# YW_001.net
KiCad netlist of a schematic drawn in Altium Designer
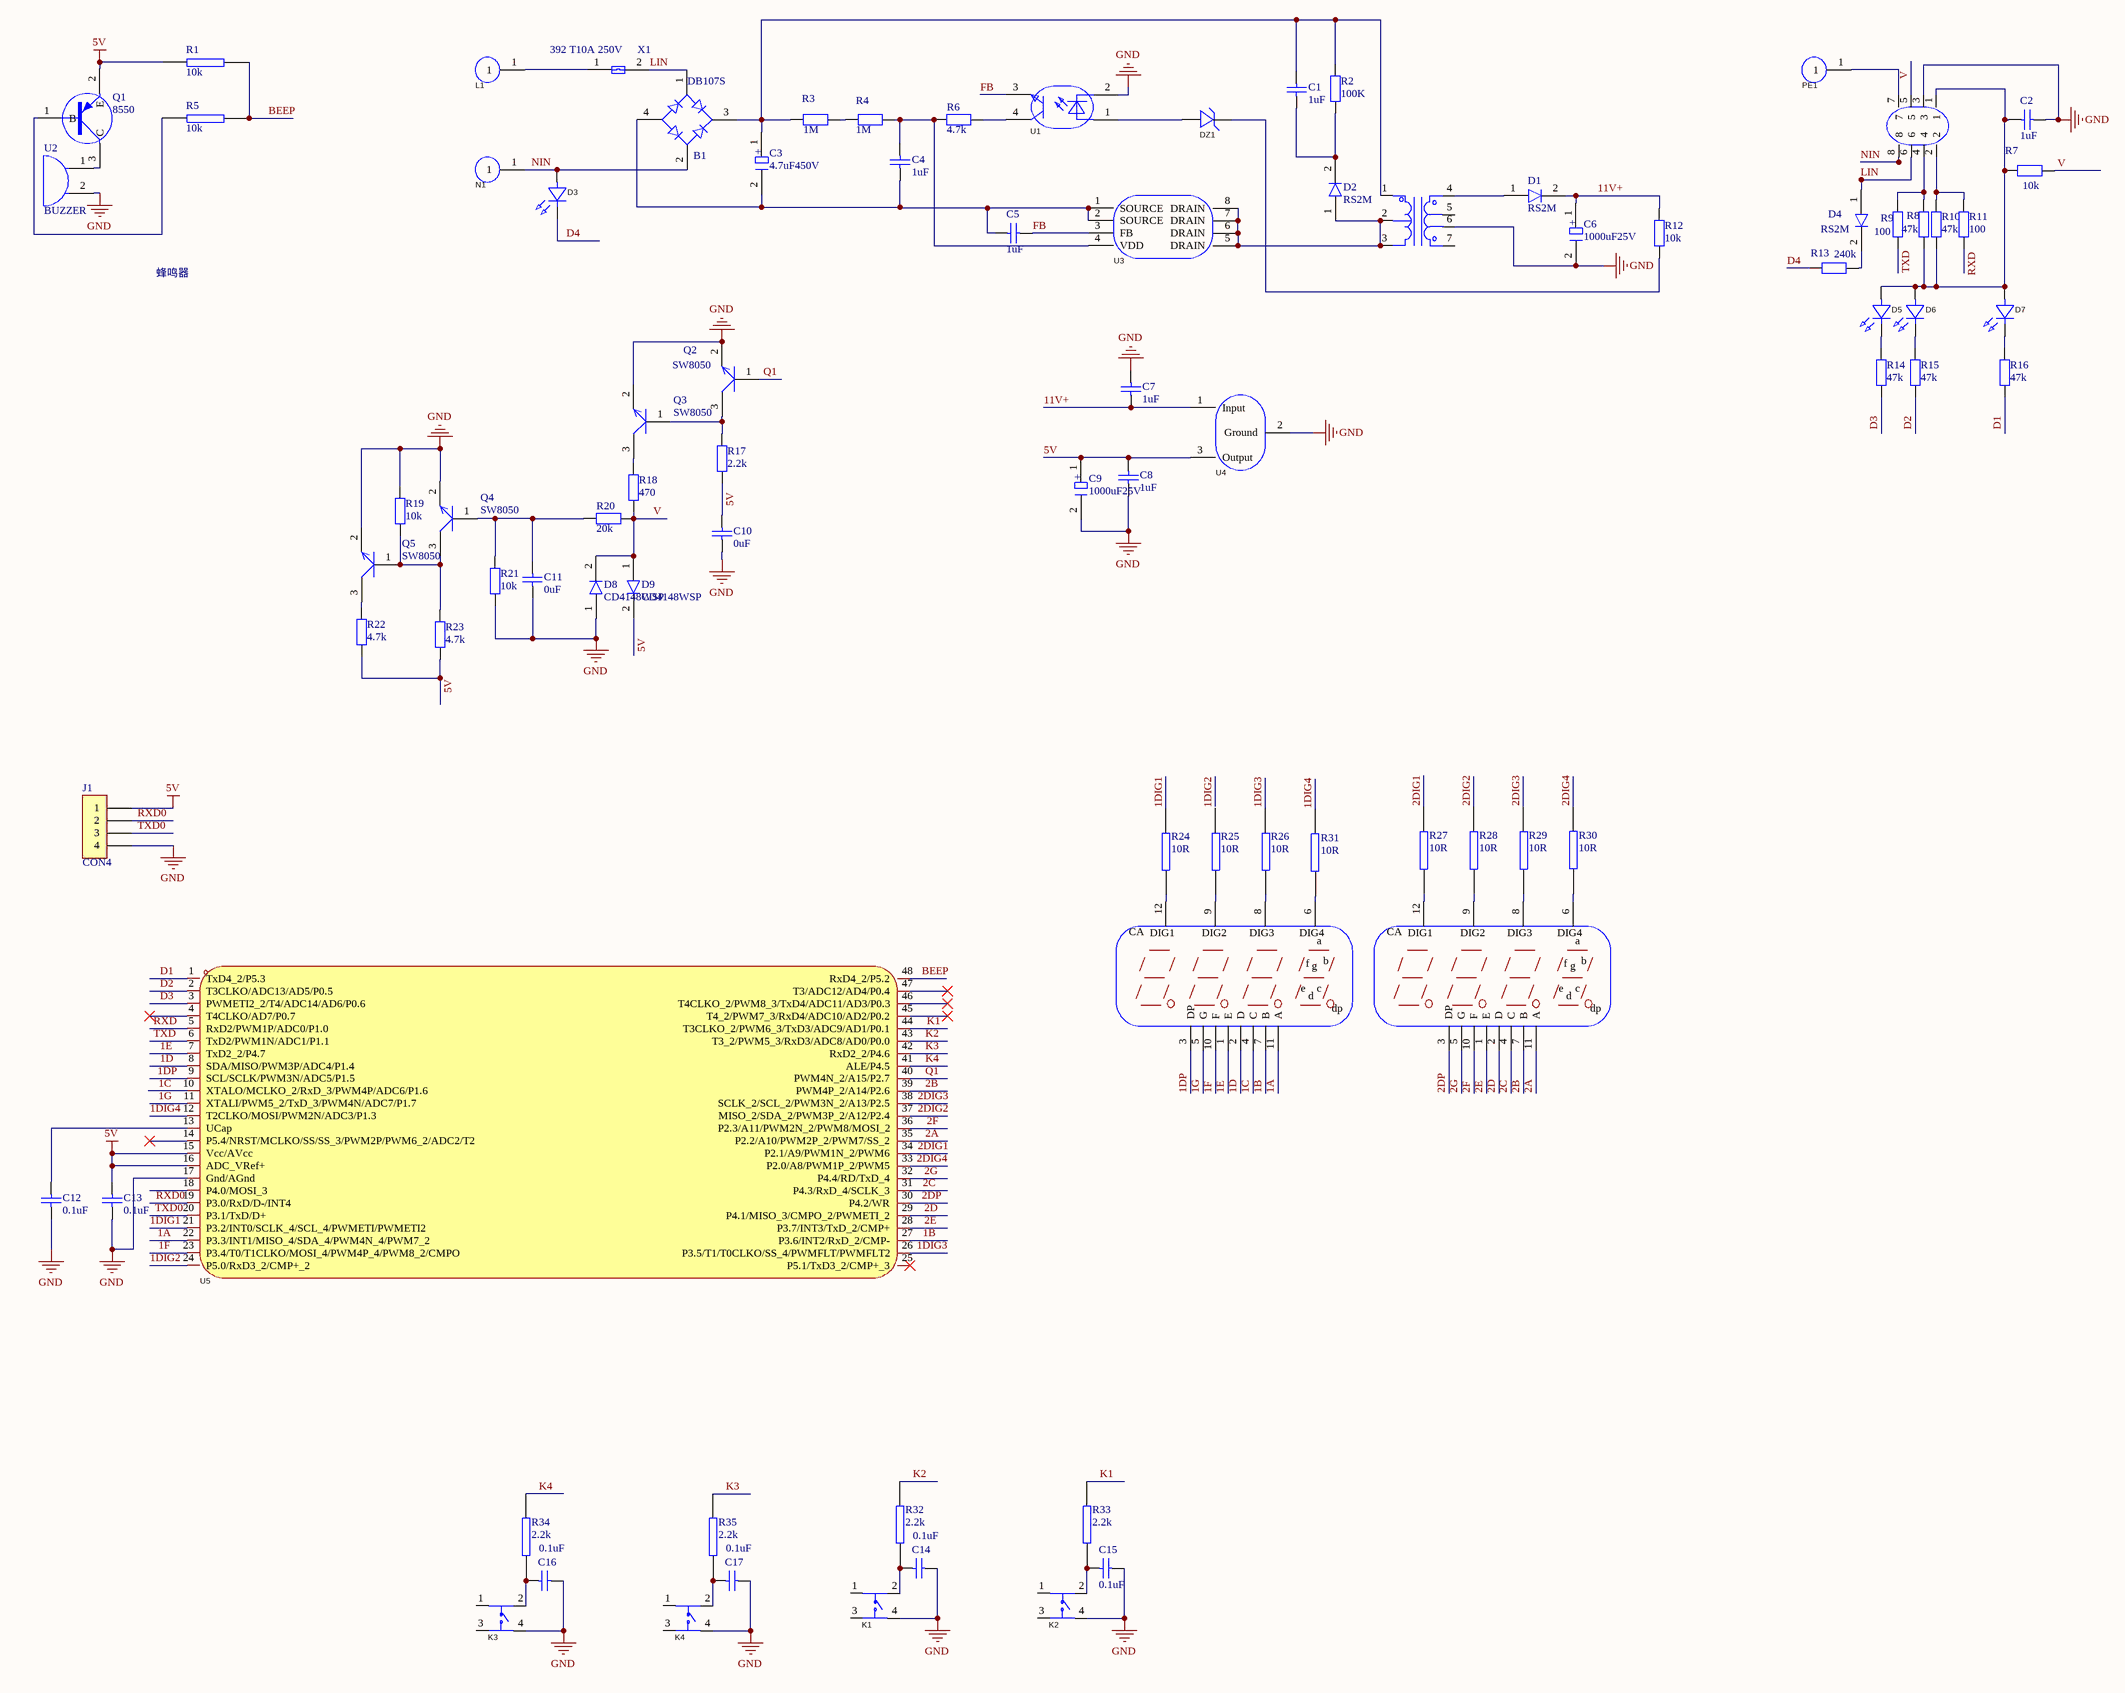
[diagram p0: YW_001.SchDoc]

(export (version "E")
  (design (tool "Eeschema 10.0.6"))
  (components
    (comp (ref "B1") (value "DB107S") (footprint "DB107S") (libsource (lib "*") (part "整流桥堆")))
    (comp (ref "C1")
      (value "1uF")
      (footprint "CAP-TH_L5.5-W4.0-P5.00-D0.5")
      (description "Capacitor")
      (fields (field (name "Comment") "102") (field (name "PUBLISHER") "Altium Limited"))
      (libsource (lib "*") (part "Cap"))
    )
    (comp (ref "C2")
      (value "1uF")
      (footprint "0805C")
      (description "Capacitor")
      (fields (field (name "Comment") "104P") (field (name "PUBLISHER") "Altium Limited"))
      (libsource (lib "*") (part "Cap"))
    )
    (comp (ref "C3")
      (value "4.7uF450V")
      (footprint "CAP-TH_BD6.3-P2.50-D1.0-FD")
      (libsource (lib "*") (part "电解电容"))
    )
    (comp (ref "C4")
      (value "1uF")
      (footprint "0805C")
      (description "Capacitor")
      (fields (field (name "PUBLISHER") "Altium Limited"))
      (libsource (lib "*") (part "Cap"))
    )
    (comp (ref "C5")
      (value "1uF")
      (footprint "0805C")
      (description "Capacitor")
      (fields (field (name "Comment") "104P") (field (name "PUBLISHER") "Altium Limited"))
      (libsource (lib "*") (part "Cap"))
    )
    (comp (ref "C6")
      (value "1000uF25V")
      (footprint "CAP-TH_BD10.0-P5.00-D1.0-FD")
      (description "CD2881081EM1017VFL")
      (libsource (lib "*") (part "电解电容"))
    )
    (comp (ref "C7")
      (value "1uF")
      (footprint "0805C")
      (description "Capacitor")
      (fields (field (name "Comment") "102") (field (name "PUBLISHER") "Altium Limited"))
      (libsource (lib "*") (part "Cap"))
    )
    (comp (ref "C8")
      (value "1uF")
      (footprint "0805C")
      (description "Capacitor")
      (fields (field (name "PUBLISHER") "Altium Limited"))
      (libsource (lib "*") (part "Cap"))
    )
    (comp (ref "C9")
      (value "1000uF25V")
      (footprint "CAP-TH_BD10.0-P5.00-D1.0-FD")
      (description "CD2881081EM1017VFL")
      (libsource (lib "*") (part "电解电容"))
    )
    (comp (ref "C10")
      (value "0uF")
      (footprint "0805C")
      (description "Capacitor")
      (fields (field (name "Comment") "102") (field (name "PUBLISHER") "Altium Limited"))
      (libsource (lib "*") (part "Cap"))
    )
    (comp (ref "C11")
      (value "0uF")
      (footprint "0805C")
      (description "Capacitor")
      (fields (field (name "Comment") "102") (field (name "PUBLISHER") "Altium Limited"))
      (libsource (lib "*") (part "Cap"))
    )
    (comp (ref "C12")
      (value "0.1uF")
      (footprint "C0603")
      (description "Capacitor")
      (fields (field (name "Comment") "104P") (field (name "PUBLISHER") "Altium Limited"))
      (libsource (lib "*") (part "Cap"))
    )
    (comp (ref "C13")
      (value "0.1uF")
      (footprint "C0603")
      (description "Capacitor")
      (fields (field (name "Comment") "104P") (field (name "PUBLISHER") "Altium Limited"))
      (libsource (lib "*") (part "Cap"))
    )
    (comp (ref "C14")
      (value "0.1uF")
      (footprint "0805C")
      (description "Capacitor")
      (fields (field (name "Comment") "104P") (field (name "PUBLISHER") "Altium Limited"))
      (libsource (lib "*") (part "Cap"))
    )
    (comp (ref "C15")
      (value "0.1uF")
      (footprint "0805C")
      (description "Capacitor")
      (fields (field (name "Comment") "104P") (field (name "PUBLISHER") "Altium Limited"))
      (libsource (lib "*") (part "Cap"))
    )
    (comp (ref "C16")
      (value "0.1uF")
      (footprint "0805C")
      (description "Capacitor")
      (fields (field (name "Comment") "104P") (field (name "PUBLISHER") "Altium Limited"))
      (libsource (lib "*") (part "Cap"))
    )
    (comp (ref "C17")
      (value "0.1uF")
      (footprint "0805C")
      (description "Capacitor")
      (fields (field (name "Comment") "104P") (field (name "PUBLISHER") "Altium Limited"))
      (libsource (lib "*") (part "Cap"))
    )
    (comp (ref "D1")
      (value "RS2M")
      (footprint "SMA-SMD_L4.4-W2.7-LS5.4-RD")
      (libsource (lib "CAMERON") (part "二极管"))
    )
    (comp (ref "D2")
      (value "RS2M")
      (footprint "SMA-SMD_L4.4-W2.7-LS5.4-RD")
      (libsource (lib "CAMERON") (part "二极管"))
    )
    (comp (ref "D3")
      (value "HLMP-1503-D0000")
      (footprint "LED-TH_BD3.0-P2.54-RD")
      (fields (field (name "MANUFACTURER") "Broadcom/AVAGO(安华高)"))
      (libsource (lib "CAMERON") (part "HLMP-1503-D0000"))
    )
    (comp (ref "D4")
      (value "RS2M")
      (footprint "SMA-SMD_L4.4-W2.7-LS5.4-RD")
      (libsource (lib "CAMERON") (part "二极管"))
    )
    (comp (ref "D5")
      (value "HLMP-1503-D0000")
      (footprint "LED-TH_BD3.0-P2.54-RD")
      (fields (field (name "MANUFACTURER") "Broadcom/AVAGO(安华高)"))
      (libsource (lib "CAMERON") (part "HLMP-1503-D0000"))
    )
    (comp (ref "D6")
      (value "HLMP-1503-D0000")
      (footprint "LED-TH_BD3.0-P2.54-RD")
      (fields (field (name "MANUFACTURER") "Broadcom/AVAGO(安华高)"))
      (libsource (lib "CAMERON") (part "HLMP-1503-D0000"))
    )
    (comp (ref "D7")
      (value "HLMP-1503-D0000")
      (footprint "LED-TH_BD3.0-P2.54-RD")
      (fields (field (name "MANUFACTURER") "Broadcom/AVAGO(安华高)"))
      (libsource (lib "CAMERON") (part "HLMP-1503-D0000"))
    )
    (comp (ref "D8") (value "CD4148WSP") (footprint "D0805-RD") (libsource (lib "CAMERON") (part "二极管")))
    (comp (ref "D9") (value "CD4148WSP") (footprint "D0805-RD") (libsource (lib "CAMERON") (part "二极管")))
    (comp (ref "DZ1")
      (value "ZMM24")
      (footprint "LL-34_L3.5-W1.5-RD")
      (fields (field (name "MANUFACTURER") "HXY MOSFET(华轩阳电子)"))
      (libsource (lib "CAMERON") (part "ZMM24_C7470923"))
    )
    (comp (ref "H1")
      (value "HC-5557-2*4AW")
      (footprint "CONN-TH_8P-P4.20_5557-2X4AW")
      (fields (field (name "MANUFACTURER") "HCTL(华灿天禄)"))
      (libsource (lib "CAMERON") (part "HC-5557-2*4AW"))
    )
    (comp (ref "J1")
      (value "CON4")
      (footprint "HDR1X4")
      (description "Connector")
      (libsource (lib "*") (part "CON4"))
    )
    (comp (ref "K1")
      (value "TS1212TPFS 250gf 072")
      (footprint "KEY-SMD_4P-L12.0-W12.0-P5.00-LS15.0")
      (fields (field (name "MANUFACTURER") "SHOU HAN(首韩)"))
      (libsource (lib "CAMERON") (part "TS1212TPFS 250gf 072"))
    )
    (comp (ref "K2")
      (value "TS1212TPFS 250gf 072")
      (footprint "KEY-SMD_4P-L12.0-W12.0-P5.00-LS15.0")
      (fields (field (name "MANUFACTURER") "SHOU HAN(首韩)"))
      (libsource (lib "CAMERON") (part "TS1212TPFS 250gf 072"))
    )
    (comp (ref "K3")
      (value "TS1212TPFS 250gf 072")
      (footprint "KEY-SMD_4P-L12.0-W12.0-P5.00-LS15.0")
      (fields (field (name "MANUFACTURER") "SHOU HAN(首韩)"))
      (libsource (lib "CAMERON") (part "TS1212TPFS 250gf 072"))
    )
    (comp (ref "K4")
      (value "TS1212TPFS 250gf 072")
      (footprint "KEY-SMD_4P-L12.0-W12.0-P5.00-LS15.0")
      (fields (field (name "MANUFACTURER") "SHOU HAN(首韩)"))
      (libsource (lib "CAMERON") (part "TS1212TPFS 250gf 072"))
    )
    (comp (ref "L1")
      (value "PZ254V-11-01P")
      (footprint "HDR-TH_1P-P2.54-V-M")
      (fields (field (name "MANUFACTURER") "XFCN(兴飞)"))
      (libsource (lib "CAMERON") (part "PZ254V-11-01P"))
    )
    (comp (ref "LED1")
      (value "FJ5461BH 橙红")
      (footprint "LED-SEG-TH_FJ5461AH")
      (fields (field (name "MANUFACTURER") "志浩"))
      (libsource (lib "CAMERON") (part "FJ5461BH 橙红"))
    )
    (comp (ref "LED2")
      (value "FJ5461BH 橙红")
      (footprint "LED-SEG-TH_FJ5461AH")
      (fields (field (name "MANUFACTURER") "志浩"))
      (libsource (lib "CAMERON") (part "FJ5461BH 橙红"))
    )
    (comp (ref "N1")
      (value "PZ254V-11-01P")
      (footprint "HDR-TH_1P-P2.54-V-M")
      (fields (field (name "MANUFACTURER") "XFCN(兴飞)"))
      (libsource (lib "altium-import") (part "root_2_PZ254V-11-01P_"))
    )
    (comp (ref "PE1")
      (value "PZ254V-11-01P")
      (footprint "HDR-TH_1P-P2.54-V-M")
      (fields (field (name "MANUFACTURER") "XFCN(兴飞)"))
      (libsource (lib "CAMERON") (part "PZ254V-11-01P"))
    )
    (comp (ref "Q1") (value "8550") (footprint "SOT-23") (libsource (lib "*") (part "PNP")))
    (comp (ref "Q2")
      (value "SW8050")
      (footprint "SOT-23 - S8550")
      (libsource (lib "CAMERON") (part "普通三级管（NPN）"))
    )
    (comp (ref "Q3")
      (value "SW8050")
      (footprint "SOT-23 - S8550")
      (libsource (lib "CAMERON") (part "普通三级管（NPN）"))
    )
    (comp (ref "Q4")
      (value "SW8050")
      (footprint "SOT-23 - S8550")
      (libsource (lib "CAMERON") (part "普通三级管（NPN）"))
    )
    (comp (ref "Q5")
      (value "SW8050")
      (footprint "SOT-23 - S8550")
      (libsource (lib "CAMERON") (part "普通三级管（NPN）"))
    )
    (comp (ref "R1") (value "10k") (footprint "0805") (libsource (lib "*") (part "RES2")))
    (comp (ref "R2")
      (value "100K")
      (footprint "0805")
      (description "Resistor")
      (fields (field (name "Comment") "Res2") (field (name "PUBLISHER") "Altium Limited"))
      (libsource (lib "") (part "Res2_1"))
    )
    (comp (ref "R3")
      (value "1M")
      (footprint "0805")
      (description "Resistor")
      (fields (field (name "Comment") "Res2") (field (name "PUBLISHER") "Altium Limited"))
      (libsource (lib "*") (part "Res2"))
    )
    (comp (ref "R4")
      (value "1M")
      (footprint "0805")
      (description "Resistor")
      (fields (field (name "Comment") "Res2") (field (name "PUBLISHER") "Altium Limited"))
      (libsource (lib "*") (part "Res2"))
    )
    (comp (ref "R5") (value "10k") (footprint "0805") (libsource (lib "*") (part "RES2")))
    (comp (ref "R6")
      (value "4.7k")
      (footprint "0805")
      (description "Resistor")
      (fields (field (name "Comment") "Res2") (field (name "PUBLISHER") "Altium Limited"))
      (libsource (lib "*") (part "Res2"))
    )
    (comp (ref "R7")
      (value "10k")
      (footprint "0805")
      (description "Resistor")
      (fields (field (name "Comment") "Res2") (field (name "PUBLISHER") "Altium Limited"))
      (libsource (lib "*") (part "Res2"))
    )
    (comp (ref "R8")
      (value "47k")
      (footprint "0805")
      (description "Resistor")
      (fields (field (name "Comment") "Res2") (field (name "PUBLISHER") "Altium Limited"))
      (libsource (lib "") (part "Res2_1"))
    )
    (comp (ref "R9")
      (value "100")
      (footprint "0805")
      (description "Resistor")
      (fields (field (name "Comment") "Res2") (field (name "PUBLISHER") "Altium Limited"))
      (libsource (lib "") (part "Res2_2"))
    )
    (comp (ref "R10")
      (value "47k")
      (footprint "0805")
      (description "Resistor")
      (fields (field (name "Comment") "Res2") (field (name "PUBLISHER") "Altium Limited"))
      (libsource (lib "") (part "Res2_1"))
    )
    (comp (ref "R11")
      (value "100")
      (footprint "0805")
      (description "Resistor")
      (fields (field (name "Comment") "Res2") (field (name "PUBLISHER") "Altium Limited"))
      (libsource (lib "") (part "Res2_2"))
    )
    (comp (ref "R12")
      (value "10k")
      (footprint "0805")
      (description "Resistor")
      (fields (field (name "Comment") "Res2") (field (name "PUBLISHER") "Altium Limited"))
      (libsource (lib "") (part "Res2_1"))
    )
    (comp (ref "R13")
      (value "240k")
      (footprint "0805")
      (description "Resistor")
      (fields (field (name "Comment") "Res2") (field (name "PUBLISHER") "Altium Limited"))
      (libsource (lib "*") (part "Res2"))
    )
    (comp (ref "R14")
      (value "47k")
      (footprint "0805")
      (description "Resistor")
      (fields (field (name "Comment") "Res2") (field (name "PUBLISHER") "Altium Limited"))
      (libsource (lib "") (part "Res2_1"))
    )
    (comp (ref "R15")
      (value "47k")
      (footprint "0805")
      (description "Resistor")
      (fields (field (name "Comment") "Res2") (field (name "PUBLISHER") "Altium Limited"))
      (libsource (lib "") (part "Res2_1"))
    )
    (comp (ref "R16")
      (value "47k")
      (footprint "0805")
      (description "Resistor")
      (fields (field (name "Comment") "Res2") (field (name "PUBLISHER") "Altium Limited"))
      (libsource (lib "") (part "Res2_1"))
    )
    (comp (ref "R17")
      (value "2.2k")
      (footprint "0805")
      (description "Resistor")
      (fields (field (name "Comment") "Res2") (field (name "PUBLISHER") "Altium Limited"))
      (libsource (lib "") (part "Res2_1"))
    )
    (comp (ref "R18")
      (value "470")
      (footprint "0805")
      (description "Resistor")
      (fields (field (name "Comment") "Res2") (field (name "PUBLISHER") "Altium Limited"))
      (libsource (lib "") (part "Res2_1"))
    )
    (comp (ref "R19")
      (value "10k")
      (footprint "0805")
      (description "Resistor")
      (fields (field (name "Comment") "Res2") (field (name "PUBLISHER") "Altium Limited"))
      (libsource (lib "") (part "Res2_1"))
    )
    (comp (ref "R20")
      (value "20k")
      (footprint "0805")
      (description "Resistor")
      (fields (field (name "Comment") "Res2") (field (name "PUBLISHER") "Altium Limited"))
      (libsource (lib "") (part "Res2_3"))
    )
    (comp (ref "R21")
      (value "10k")
      (footprint "0805")
      (description "Resistor")
      (fields (field (name "Comment") "Res2") (field (name "PUBLISHER") "Altium Limited"))
      (libsource (lib "") (part "Res2_2"))
    )
    (comp (ref "R22")
      (value "4.7k")
      (footprint "0805")
      (description "Resistor")
      (fields (field (name "Comment") "Res2") (field (name "PUBLISHER") "Altium Limited"))
      (libsource (lib "") (part "Res2_1"))
    )
    (comp (ref "R23")
      (value "4.7k")
      (footprint "0805")
      (description "Resistor")
      (fields (field (name "Comment") "Res2") (field (name "PUBLISHER") "Altium Limited"))
      (libsource (lib "") (part "Res2_1"))
    )
    (comp (ref "R24") (value "10R") (footprint "R0603") (libsource (lib "*") (part "RES2")))
    (comp (ref "R25") (value "10R") (footprint "R0603") (libsource (lib "*") (part "RES2")))
    (comp (ref "R26") (value "10R") (footprint "R0603") (libsource (lib "*") (part "RES2")))
    (comp (ref "R27") (value "10R") (footprint "R0603") (libsource (lib "*") (part "RES2")))
    (comp (ref "R28") (value "10R") (footprint "R0603") (libsource (lib "*") (part "RES2")))
    (comp (ref "R29") (value "10R") (footprint "R0603") (libsource (lib "*") (part "RES2")))
    (comp (ref "R30") (value "10R") (footprint "R0603") (libsource (lib "*") (part "RES2")))
    (comp (ref "R31") (value "10R") (footprint "R0603") (libsource (lib "*") (part "RES2")))
    (comp (ref "R32") (value "2.2k") (footprint "0805") (libsource (lib "*") (part "RES2")))
    (comp (ref "R33") (value "2.2k") (footprint "0805") (libsource (lib "*") (part "RES2")))
    (comp (ref "R34") (value "2.2k") (footprint "0805") (libsource (lib "*") (part "RES2")))
    (comp (ref "R35") (value "2.2k") (footprint "0805") (libsource (lib "*") (part "RES2")))
    (comp (ref "U1")
      (value "EL817S1(C)(TU)-F")
      (footprint "OPTO-SMD-4_L4.6-W6.5-P2.54-LS10.3-TL")
      (fields (field (name "MANUFACTURER") "EVERLIGHT(亿光)"))
      (libsource (lib "CAMERON") (part "EL817S1(C)(TU)-F"))
    )
    (comp (ref "U2")
      (value "BUZZER")
      (footprint "BUZZ-7.6/12")
      (description "Buzzer")
      (libsource (lib "*") (part "BUZZER"))
    )
    (comp (ref "U3")
      (value "VIPER12ASTR-E")
      (footprint "SOIC-8_L5.0-W4.0-P1.27-LS6.0-BL")
      (fields (field (name "MANUFACTURER") "ST(意法半导体)"))
      (libsource (lib "CAMERON") (part "VIPER12ASTR-E"))
    )
    (comp (ref "U4")
      (value "MC7805CDTRKG")
      (footprint "TO-252-2_L6.6-W6.1-P4.58-LS9.9-TL")
      (fields (field (name "MANUFACTURER") "onsemi(安森美)"))
      (libsource (lib "CAMERON") (part "MC7805CDTRKG"))
    )
    (comp (ref "U5")
      (value "STC8H8K64U-45I-LQFP48")
      (footprint "LQFP-48_L7.0-W7.0-P0.50-LS9.0-BL")
      (fields (field (name "MANUFACTURER") "STC(宏晶)"))
      (libsource (lib "CAMERON") (part "STC8H8K64U-45I-LQFP48"))
    )
    (comp (ref "USB1")
      (value "ECO2017SEO-X16V015")
      (footprint "XFMR-TH_ECO2017SEO-X16V015")
      (fields (field (name "MANUFACTURER") "TDK"))
      (libsource (lib "CAMERON") (part "ECO2017SEO-X16V015"))
    )
    (comp (ref "X1") (value "392 T10A 250V") (footprint "FUSE") (libsource (lib "*") (part "保险丝")))
  )
  (nets
    (net (code "1") (name "/1A") (class "Default")
      (node (ref "LED1") (pin "11") (pinfunction "A_11") (pintype "passive"))
      (node (ref "U5") (pin "22") (pinfunction "P3.3/INT1/MISO_4/SDA_4/PWM4N_4/PWM7_2_22") (pintype "passive"))
    )
    (net (code "2") (name "/1B") (class "Default")
      (node (ref "LED1") (pin "7") (pinfunction "B_7") (pintype "passive"))
      (node (ref "U5") (pin "27") (pinfunction "P3.6/INT2/RxD_2/CMP-_27") (pintype "passive"))
    )
    (net (code "3") (name "/1C") (class "Default")
      (node (ref "LED1") (pin "4") (pinfunction "C_4") (pintype "passive"))
      (node (ref "U5") (pin "10") (pinfunction "XTALO/MCLKO_2/RxD_3/PWM4P/ADC6/P1.6_10") (pintype "passive"))
    )
    (net (code "4") (name "/1D") (class "Default")
      (node (ref "LED1") (pin "2") (pinfunction "D_2") (pintype "passive"))
      (node (ref "U5") (pin "8") (pinfunction "SDA/MISO/PWM3P/ADC4/P1.4_8") (pintype "passive"))
    )
    (net (code "5") (name "/1DIG1") (class "Default")
      (node (ref "R24") (pin "1") (pinfunction "1_1") (pintype "passive"))
      (node (ref "U5") (pin "21") (pinfunction "P3.2/INT0/SCLK_4/SCL_4/PWMETI/PWMETI2_21") (pintype "passive"))
    )
    (net (code "6") (name "/1DIG2") (class "Default")
      (node (ref "R25") (pin "1") (pinfunction "1_1") (pintype "passive"))
      (node (ref "U5") (pin "24") (pinfunction "P5.0/RxD3_2/CMP+_2_24") (pintype "passive"))
    )
    (net (code "7") (name "/1DIG3") (class "Default")
      (node (ref "R26") (pin "1") (pinfunction "1_1") (pintype "passive"))
      (node (ref "U5") (pin "26") (pinfunction "P3.5/T1/T0CLKO/SS_4/PWMFLT/PWMFLT2_26") (pintype "passive"))
    )
    (net (code "8") (name "/1DIG4") (class "Default")
      (node (ref "R31") (pin "2") (pinfunction "2_2") (pintype "passive"))
      (node (ref "U5") (pin "12") (pinfunction "T2CLKO/MOSI/PWM2N/ADC3/P1.3_12") (pintype "passive"))
    )
    (net (code "9") (name "/1DP") (class "Default")
      (node (ref "LED1") (pin "3") (pinfunction "DP_3") (pintype "passive"))
      (node (ref "U5") (pin "9") (pinfunction "SCL/SCLK/PWM3N/ADC5/P1.5_9") (pintype "passive"))
    )
    (net (code "10") (name "/1E") (class "Default")
      (node (ref "LED1") (pin "1") (pinfunction "E_1") (pintype "passive"))
      (node (ref "U5") (pin "7") (pinfunction "TxD2_2/P4.7_7") (pintype "passive"))
    )
    (net (code "11") (name "/1F") (class "Default")
      (node (ref "LED1") (pin "10") (pinfunction "F_10") (pintype "passive"))
      (node (ref "U5") (pin "23") (pinfunction "P3.4/T0/T1CLKO/MOSI_4/PWM4P_4/PWM8_2/CMPO_23") (pintype "passive"))
    )
    (net (code "12") (name "/1G") (class "Default")
      (node (ref "LED1") (pin "5") (pinfunction "G_5") (pintype "passive"))
      (node (ref "U5") (pin "11") (pinfunction "XTALI/PWM5_2/TxD_3/PWM4N/ADC7/P1.7_11") (pintype "passive"))
    )
    (net (code "13") (name "/2A") (class "Default")
      (node (ref "LED2") (pin "11") (pinfunction "A_11") (pintype "passive"))
      (node (ref "U5") (pin "35") (pinfunction "P2.2/A10/PWM2P_2/PWM7/SS_2_35") (pintype "passive"))
    )
    (net (code "14") (name "/2B") (class "Default")
      (node (ref "LED2") (pin "7") (pinfunction "B_7") (pintype "passive"))
      (node (ref "U5") (pin "39") (pinfunction "PWM4P_2/A14/P2.6_39") (pintype "passive"))
    )
    (net (code "15") (name "/2C") (class "Default")
      (node (ref "LED2") (pin "4") (pinfunction "C_4") (pintype "passive"))
      (node (ref "U5") (pin "31") (pinfunction "P4.3/RxD_4/SCLK_3_31") (pintype "passive"))
    )
    (net (code "16") (name "/2D") (class "Default")
      (node (ref "LED2") (pin "2") (pinfunction "D_2") (pintype "passive"))
      (node (ref "U5") (pin "29") (pinfunction "P4.1/MISO_3/CMPO_2/PWMETI_2_29") (pintype "passive"))
    )
    (net (code "17") (name "/2DIG1") (class "Default")
      (node (ref "R27") (pin "1") (pinfunction "1_1") (pintype "passive"))
      (node (ref "U5") (pin "34") (pinfunction "P2.1/A9/PWM1N_2/PWM6_34") (pintype "passive"))
    )
    (net (code "18") (name "/2DIG2") (class "Default")
      (node (ref "R28") (pin "1") (pinfunction "1_1") (pintype "passive"))
      (node (ref "U5") (pin "37") (pinfunction "MISO_2/SDA_2/PWM3P_2/A12/P2.4_37") (pintype "passive"))
    )
    (net (code "19") (name "/2DIG3") (class "Default")
      (node (ref "R29") (pin "1") (pinfunction "1_1") (pintype "passive"))
      (node (ref "U5") (pin "38") (pinfunction "SCLK_2/SCL_2/PWM3N_2/A13/P2.5_38") (pintype "passive"))
    )
    (net (code "20") (name "/2DIG4") (class "Default")
      (node (ref "R30") (pin "2") (pinfunction "2_2") (pintype "passive"))
      (node (ref "U5") (pin "33") (pinfunction "P2.0/A8/PWM1P_2/PWM5_33") (pintype "passive"))
    )
    (net (code "21") (name "/2DP") (class "Default")
      (node (ref "LED2") (pin "3") (pinfunction "DP_3") (pintype "passive"))
      (node (ref "U5") (pin "30") (pinfunction "P4.2/WR_30") (pintype "passive"))
    )
    (net (code "22") (name "/2E") (class "Default")
      (node (ref "LED2") (pin "1") (pinfunction "E_1") (pintype "passive"))
      (node (ref "U5") (pin "28") (pinfunction "P3.7/INT3/TxD_2/CMP+_28") (pintype "passive"))
    )
    (net (code "23") (name "/2F") (class "Default")
      (node (ref "LED2") (pin "10") (pinfunction "F_10") (pintype "passive"))
      (node (ref "U5") (pin "36") (pinfunction "P2.3/A11/PWM2N_2/PWM8/MOSI_2_36") (pintype "passive"))
    )
    (net (code "24") (name "/2G") (class "Default")
      (node (ref "LED2") (pin "5") (pinfunction "G_5") (pintype "passive"))
      (node (ref "U5") (pin "32") (pinfunction "P4.4/RD/TxD_4_32") (pintype "passive"))
    )
    (net (code "25") (name "/11V+") (class "Default")
      (node (ref "C6") (pin "1") (pintype "passive"))
      (node (ref "C7") (pin "2") (pinfunction "2_2") (pintype "passive"))
      (node (ref "D1") (pin "2") (pintype "passive"))
      (node (ref "R12") (pin "1") (pinfunction "1_1") (pintype "passive"))
      (node (ref "U4") (pin "1") (pinfunction "Input_1") (pintype "passive"))
    )
    (net (code "26") (name "/BEEP") (class "Default")
      (node (ref "R1") (pin "2") (pinfunction "2_2") (pintype "passive"))
      (node (ref "R5") (pin "2") (pinfunction "2_2") (pintype "passive"))
      (node (ref "U5") (pin "48") (pinfunction "RxD4_2/P5.2_48") (pintype "passive"))
    )
    (net (code "27") (name "/D1") (class "Default")
      (node (ref "R16") (pin "2") (pinfunction "2_2") (pintype "passive"))
      (node (ref "U5") (pin "1") (pinfunction "TxD4_2/P5.3_1") (pintype "passive"))
    )
    (net (code "28") (name "/D2") (class "Default")
      (node (ref "R15") (pin "2") (pinfunction "2_2") (pintype "passive"))
      (node (ref "U5") (pin "2") (pinfunction "T3CLKO/ADC13/AD5/P0.5_2") (pintype "passive"))
    )
    (net (code "29") (name "/D3") (class "Default")
      (node (ref "R14") (pin "2") (pinfunction "2_2") (pintype "passive"))
      (node (ref "U5") (pin "3") (pinfunction "PWMETI2_2/T4/ADC14/AD6/P0.6_3") (pintype "passive"))
    )
    (net (code "30") (name "/D4") (class "Default")
      (node (ref "D3") (pin "1") (pinfunction "K_1") (pintype "passive"))
      (node (ref "R13") (pin "2") (pinfunction "2_2") (pintype "passive"))
    )
    (net (code "31") (name "/FB") (class "Default")
      (node (ref "C5") (pin "1") (pinfunction "1_1") (pintype "passive"))
      (node (ref "U1") (pin "3") (pinfunction "EM_3") (pintype "passive"))
      (node (ref "U3") (pin "3") (pinfunction "FB_3") (pintype "passive"))
    )
    (net (code "32") (name "/K1") (class "Default")
      (node (ref "R33") (pin "2") (pinfunction "2_2") (pintype "passive"))
      (node (ref "U5") (pin "44") (pinfunction "T3CLKO_2/PWM6_3/TxD3/ADC9/AD1/P0.1_44") (pintype "passive"))
    )
    (net (code "33") (name "/K2") (class "Default")
      (node (ref "R32") (pin "2") (pinfunction "2_2") (pintype "passive"))
      (node (ref "U5") (pin "43") (pinfunction "T3_2/PWM5_3/RxD3/ADC8/AD0/P0.0_43") (pintype "passive"))
    )
    (net (code "34") (name "/K3") (class "Default")
      (node (ref "R35") (pin "2") (pinfunction "2_2") (pintype "passive"))
      (node (ref "U5") (pin "42") (pinfunction "RxD2_2/P4.6_42") (pintype "passive"))
    )
    (net (code "35") (name "/K4") (class "Default")
      (node (ref "R34") (pin "2") (pinfunction "2_2") (pintype "passive"))
      (node (ref "U5") (pin "41") (pinfunction "ALE/P4.5_41") (pintype "passive"))
    )
    (net (code "36") (name "/LIN") (class "Default")
      (node (ref "B1") (pin "1") (pintype "passive"))
      (node (ref "D4") (pin "1") (pintype "passive"))
      (node (ref "H1") (pin "6") (pinfunction "6_6") (pintype "passive"))
      (node (ref "X1") (pin "2") (pintype "passive"))
    )
    (net (code "37") (name "/NIN") (class "Default")
      (node (ref "B1") (pin "2") (pintype "passive"))
      (node (ref "D3") (pin "2") (pinfunction "A_2") (pintype "passive"))
      (node (ref "H1") (pin "8") (pinfunction "8_8") (pintype "passive"))
      (node (ref "N1") (pin "1") (pinfunction "1_1") (pintype "passive"))
    )
    (net (code "38") (name "/Q1") (class "Default")
      (node (ref "Q2") (pin "1") (pinfunction "B_1") (pintype "passive"))
      (node (ref "U5") (pin "40") (pinfunction "PWM4N_2/A15/P2.7_40") (pintype "passive"))
    )
    (net (code "39") (name "/RXD") (class "Default")
      (node (ref "R11") (pin "1") (pinfunction "1_1") (pintype "passive"))
      (node (ref "U5") (pin "5") (pinfunction "RxD2/PWM1P/ADC0/P1.0_5") (pintype "passive"))
    )
    (net (code "40") (name "/RXD0") (class "Default")
      (node (ref "J1") (pin "2") (pinfunction "2_2") (pintype "passive"))
      (node (ref "U5") (pin "19") (pinfunction "P3.0/RxD/D-/INT4_19") (pintype "passive"))
    )
    (net (code "41") (name "/TXD") (class "Default")
      (node (ref "R9") (pin "1") (pinfunction "1_1") (pintype "passive"))
      (node (ref "U5") (pin "6") (pinfunction "TxD2/PWM1N/ADC1/P1.1_6") (pintype "passive"))
    )
    (net (code "42") (name "/TXD0") (class "Default")
      (node (ref "J1") (pin "3") (pinfunction "3_3") (pintype "passive"))
      (node (ref "U5") (pin "20") (pinfunction "P3.1/TxD/D+_20") (pintype "passive"))
    )
    (net (code "43") (name "/V") (class "Default")
      (node (ref "D8") (pin "2") (pintype "passive"))
      (node (ref "D9") (pin "1") (pintype "passive"))
      (node (ref "H1") (pin "5") (pinfunction "5_5") (pintype "passive"))
      (node (ref "R18") (pin "2") (pinfunction "2_2") (pintype "passive"))
      (node (ref "R20") (pin "2") (pinfunction "2_2") (pintype "passive"))
      (node (ref "R7") (pin "1") (pinfunction "1_1") (pintype "passive"))
    )
    (net (code "44") (name "5V") (class "Default")
      (node (ref "C10") (pin "1") (pinfunction "1_1") (pintype "passive"))
      (node (ref "C13") (pin "2") (pinfunction "2_2") (pintype "passive"))
      (node (ref "C8") (pin "1") (pinfunction "1_1") (pintype "passive"))
      (node (ref "C9") (pin "1") (pintype "passive"))
      (node (ref "D9") (pin "2") (pintype "passive"))
      (node (ref "J1") (pin "1") (pinfunction "1_1") (pintype "passive"))
      (node (ref "Q1") (pin "2") (pinfunction "E_2") (pintype "passive"))
      (node (ref "R1") (pin "1") (pinfunction "1_1") (pintype "passive"))
      (node (ref "R17") (pin "2") (pinfunction "2_2") (pintype "passive"))
      (node (ref "R22") (pin "2") (pinfunction "2_2") (pintype "passive"))
      (node (ref "R23") (pin "2") (pinfunction "2_2") (pintype "passive"))
      (node (ref "U4") (pin "3") (pinfunction "Output_3") (pintype "passive"))
      (node (ref "U5") (pin "15") (pinfunction "Vcc/AVcc_15") (pintype "passive"))
      (node (ref "U5") (pin "16") (pinfunction "ADC_VRef+_16") (pintype "passive"))
    )
    (net (code "45") (name "GND") (class "Default")
      (node (ref "C10") (pin "2") (pinfunction "2_2") (pintype "passive"))
      (node (ref "C11") (pin "2") (pinfunction "2_2") (pintype "passive"))
      (node (ref "C12") (pin "1") (pinfunction "1_1") (pintype "passive"))
      (node (ref "C13") (pin "1") (pinfunction "1_1") (pintype "passive"))
      (node (ref "C14") (pin "2") (pinfunction "2_2") (pintype "passive"))
      (node (ref "C15") (pin "2") (pinfunction "2_2") (pintype "passive"))
      (node (ref "C16") (pin "2") (pinfunction "2_2") (pintype "passive"))
      (node (ref "C17") (pin "2") (pinfunction "2_2") (pintype "passive"))
      (node (ref "C2") (pin "1") (pinfunction "1_1") (pintype "passive"))
      (node (ref "C6") (pin "2") (pintype "passive"))
      (node (ref "C7") (pin "1") (pinfunction "1_1") (pintype "passive"))
      (node (ref "C8") (pin "2") (pinfunction "2_2") (pintype "passive"))
      (node (ref "C9") (pin "2") (pintype "passive"))
      (node (ref "D8") (pin "1") (pintype "passive"))
      (node (ref "H1") (pin "3") (pinfunction "3_3") (pintype "passive"))
      (node (ref "J1") (pin "4") (pinfunction "4_4") (pintype "passive"))
      (node (ref "K1") (pin "4") (pinfunction "4_4") (pintype "passive"))
      (node (ref "K2") (pin "4") (pinfunction "4_4") (pintype "passive"))
      (node (ref "K3") (pin "4") (pinfunction "4_4") (pintype "passive"))
      (node (ref "K4") (pin "4") (pinfunction "4_4") (pintype "passive"))
      (node (ref "Q2") (pin "2") (pinfunction "E_2") (pintype "passive"))
      (node (ref "Q3") (pin "2") (pinfunction "E_2") (pintype "passive"))
      (node (ref "Q4") (pin "2") (pinfunction "E_2") (pintype "passive"))
      (node (ref "Q5") (pin "2") (pinfunction "E_2") (pintype "passive"))
      (node (ref "R19") (pin "1") (pinfunction "1_1") (pintype "passive"))
      (node (ref "R21") (pin "1") (pinfunction "1_1") (pintype "passive"))
      (node (ref "U1") (pin "2") (pinfunction "CAT_2") (pintype "passive"))
      (node (ref "U2") (pin "2") (pinfunction "B_2") (pintype "passive"))
      (node (ref "U4") (pin "2") (pinfunction "Ground_2") (pintype "passive"))
      (node (ref "U5") (pin "17") (pinfunction "Gnd/AGnd_17") (pintype "passive"))
      (node (ref "USB1") (pin "6") (pinfunction "2_6") (pintype "passive"))
    )
    (net (code "46") (name "Net-(B1-Pad4)") (class "Default")
      (node (ref "B1") (pin "4") (pintype "passive"))
      (node (ref "C3") (pin "2") (pintype "passive"))
      (node (ref "C4") (pin "2") (pinfunction "2_2") (pintype "passive"))
      (node (ref "C5") (pin "2") (pinfunction "2_2") (pintype "passive"))
      (node (ref "U3") (pin "1") (pinfunction "SOURCE_1") (pintype "passive"))
      (node (ref "U3") (pin "2") (pinfunction "SOURCE_2") (pintype "passive"))
    )
    (net (code "47") (name "Net-(C1-Pad2)") (class "Default")
      (node (ref "C1") (pin "2") (pinfunction "2_2") (pintype "passive"))
      (node (ref "D2") (pin "2") (pintype "passive"))
      (node (ref "R2") (pin "2") (pinfunction "2_2") (pintype "passive"))
    )
    (net (code "48") (name "Net-(C14-Pad1)") (class "Default")
      (node (ref "C14") (pin "1") (pinfunction "1_1") (pintype "passive"))
      (node (ref "K1") (pin "2") (pinfunction "2_2") (pintype "passive"))
      (node (ref "R32") (pin "1") (pinfunction "1_1") (pintype "passive"))
    )
    (net (code "49") (name "Net-(C15-Pad1)") (class "Default")
      (node (ref "C15") (pin "1") (pinfunction "1_1") (pintype "passive"))
      (node (ref "K2") (pin "2") (pinfunction "2_2") (pintype "passive"))
      (node (ref "R33") (pin "1") (pinfunction "1_1") (pintype "passive"))
    )
    (net (code "50") (name "Net-(C16-Pad1)") (class "Default")
      (node (ref "C16") (pin "1") (pinfunction "1_1") (pintype "passive"))
      (node (ref "K3") (pin "2") (pinfunction "2_2") (pintype "passive"))
      (node (ref "R34") (pin "1") (pinfunction "1_1") (pintype "passive"))
    )
    (net (code "51") (name "Net-(C17-Pad1)") (class "Default")
      (node (ref "C17") (pin "1") (pinfunction "1_1") (pintype "passive"))
      (node (ref "K4") (pin "2") (pinfunction "2_2") (pintype "passive"))
      (node (ref "R35") (pin "1") (pinfunction "1_1") (pintype "passive"))
    )
    (net (code "52") (name "Net-(D4-Pad2)") (class "Default")
      (node (ref "D4") (pin "2") (pintype "passive"))
      (node (ref "R13") (pin "1") (pinfunction "1_1") (pintype "passive"))
    )
    (net (code "53") (name "Net-(D5-A)") (class "Default")
      (node (ref "C2") (pin "2") (pinfunction "2_2") (pintype "passive"))
      (node (ref "D5") (pin "2") (pinfunction "A_2") (pintype "passive"))
      (node (ref "D6") (pin "2") (pinfunction "A_2") (pintype "passive"))
      (node (ref "D7") (pin "2") (pinfunction "A_2") (pintype "passive"))
      (node (ref "H1") (pin "1") (pinfunction "1_1") (pintype "passive"))
      (node (ref "R10") (pin "2") (pinfunction "2_2") (pintype "passive"))
      (node (ref "R7") (pin "2") (pinfunction "2_2") (pintype "passive"))
      (node (ref "R8") (pin "2") (pinfunction "2_2") (pintype "passive"))
    )
    (net (code "54") (name "Net-(D5-K)") (class "Default")
      (node (ref "D5") (pin "1") (pinfunction "K_1") (pintype "passive"))
      (node (ref "R14") (pin "1") (pinfunction "1_1") (pintype "passive"))
    )
    (net (code "55") (name "Net-(D6-K)") (class "Default")
      (node (ref "D6") (pin "1") (pinfunction "K_1") (pintype "passive"))
      (node (ref "R15") (pin "1") (pinfunction "1_1") (pintype "passive"))
    )
    (net (code "56") (name "Net-(D7-K)") (class "Default")
      (node (ref "D7") (pin "1") (pinfunction "K_1") (pintype "passive"))
      (node (ref "R16") (pin "1") (pinfunction "1_1") (pintype "passive"))
    )
    (net (code "57") (name "Net-(DZ1-A)") (class "Default")
      (node (ref "DZ1") (pin "2") (pinfunction "A_2") (pintype "passive"))
      (node (ref "U1") (pin "1") (pinfunction "AN_1") (pintype "passive"))
    )
    (net (code "58") (name "Net-(DZ1-C)") (class "Default")
      (node (ref "DZ1") (pin "1") (pinfunction "C_1") (pintype "passive"))
      (node (ref "R12") (pin "2") (pinfunction "2_2") (pintype "passive"))
    )
    (net (code "59") (name "Net-(H1-Pad2)") (class "Default")
      (node (ref "H1") (pin "2") (pinfunction "2_2") (pintype "passive"))
      (node (ref "R10") (pin "1") (pinfunction "1_1") (pintype "passive"))
      (node (ref "R11") (pin "2") (pinfunction "2_2") (pintype "passive"))
    )
    (net (code "60") (name "Net-(H1-Pad4)") (class "Default")
      (node (ref "H1") (pin "4") (pinfunction "4_4") (pintype "passive"))
      (node (ref "R8") (pin "1") (pinfunction "1_1") (pintype "passive"))
      (node (ref "R9") (pin "2") (pinfunction "2_2") (pintype "passive"))
    )
    (net (code "61") (name "Net-(H1-Pad7)") (class "Default")
      (node (ref "H1") (pin "7") (pinfunction "7_7") (pintype "passive"))
      (node (ref "PE1") (pin "1") (pinfunction "1_1") (pintype "passive"))
    )
    (net (code "62") (name "Net-(L1-Pad1)") (class "Default")
      (node (ref "L1") (pin "1") (pinfunction "1_1") (pintype "passive"))
      (node (ref "X1") (pin "1") (pintype "passive"))
    )
    (net (code "63") (name "Net-(LED1-DIG1)") (class "Default")
      (node (ref "LED1") (pin "12") (pinfunction "DIG1_12") (pintype "passive"))
      (node (ref "R24") (pin "2") (pinfunction "2_2") (pintype "passive"))
    )
    (net (code "64") (name "Net-(LED1-DIG2)") (class "Default")
      (node (ref "LED1") (pin "9") (pinfunction "DIG2_9") (pintype "passive"))
      (node (ref "R25") (pin "2") (pinfunction "2_2") (pintype "passive"))
    )
    (net (code "65") (name "Net-(LED1-DIG3)") (class "Default")
      (node (ref "LED1") (pin "8") (pinfunction "DIG3_8") (pintype "passive"))
      (node (ref "R26") (pin "2") (pinfunction "2_2") (pintype "passive"))
    )
    (net (code "66") (name "Net-(LED1-DIG4)") (class "Default")
      (node (ref "LED1") (pin "6") (pinfunction "DIG4_6") (pintype "passive"))
      (node (ref "R31") (pin "1") (pinfunction "1_1") (pintype "passive"))
    )
    (net (code "67") (name "Net-(LED2-DIG1)") (class "Default")
      (node (ref "LED2") (pin "12") (pinfunction "DIG1_12") (pintype "passive"))
      (node (ref "R27") (pin "2") (pinfunction "2_2") (pintype "passive"))
    )
    (net (code "68") (name "Net-(LED2-DIG2)") (class "Default")
      (node (ref "LED2") (pin "9") (pinfunction "DIG2_9") (pintype "passive"))
      (node (ref "R28") (pin "2") (pinfunction "2_2") (pintype "passive"))
    )
    (net (code "69") (name "Net-(LED2-DIG3)") (class "Default")
      (node (ref "LED2") (pin "8") (pinfunction "DIG3_8") (pintype "passive"))
      (node (ref "R29") (pin "2") (pinfunction "2_2") (pintype "passive"))
    )
    (net (code "70") (name "Net-(LED2-DIG4)") (class "Default")
      (node (ref "LED2") (pin "6") (pinfunction "DIG4_6") (pintype "passive"))
      (node (ref "R30") (pin "1") (pinfunction "1_1") (pintype "passive"))
    )
    (net (code "71") (name "Net-(Q1-B)") (class "Default")
      (node (ref "Q1") (pin "1") (pinfunction "B_1") (pintype "passive"))
      (node (ref "R5") (pin "1") (pinfunction "1_1") (pintype "passive"))
    )
    (net (code "72") (name "Net-(Q1-C)") (class "Default")
      (node (ref "Q1") (pin "3") (pinfunction "C_3") (pintype "passive"))
      (node (ref "U2") (pin "1") (pinfunction "A_1") (pintype "passive"))
    )
    (net (code "73") (name "Net-(Q2-C)") (class "Default")
      (node (ref "Q2") (pin "3") (pinfunction "C_3") (pintype "passive"))
      (node (ref "Q3") (pin "1") (pinfunction "B_1") (pintype "passive"))
      (node (ref "R17") (pin "1") (pinfunction "1_1") (pintype "passive"))
    )
    (net (code "74") (name "Net-(Q3-C)") (class "Default")
      (node (ref "Q3") (pin "3") (pinfunction "C_3") (pintype "passive"))
      (node (ref "R18") (pin "1") (pinfunction "1_1") (pintype "passive"))
    )
    (net (code "75") (name "Net-(Q4-B)") (class "Default")
      (node (ref "C11") (pin "1") (pinfunction "1_1") (pintype "passive"))
      (node (ref "Q4") (pin "1") (pinfunction "B_1") (pintype "passive"))
      (node (ref "R20") (pin "1") (pinfunction "1_1") (pintype "passive"))
      (node (ref "R21") (pin "2") (pinfunction "2_2") (pintype "passive"))
    )
    (net (code "76") (name "Net-(Q4-C)") (class "Default")
      (node (ref "Q4") (pin "3") (pinfunction "C_3") (pintype "passive"))
      (node (ref "Q5") (pin "1") (pinfunction "B_1") (pintype "passive"))
      (node (ref "R19") (pin "2") (pinfunction "2_2") (pintype "passive"))
      (node (ref "R23") (pin "1") (pinfunction "1_1") (pintype "passive"))
    )
    (net (code "77") (name "Net-(Q5-C)") (class "Default")
      (node (ref "Q5") (pin "3") (pinfunction "C_3") (pintype "passive"))
      (node (ref "R22") (pin "1") (pinfunction "1_1") (pintype "passive"))
    )
    (net (code "78") (name "Net-(R3-Pad1)") (class "Default")
      (node (ref "R3") (pin "1") (pinfunction "1_1") (pintype "passive"))
      (node (ref "R4") (pin "2") (pinfunction "2_2") (pintype "passive"))
    )
    (net (code "79") (name "Net-(U1-COL)") (class "Default")
      (node (ref "R6") (pin "1") (pinfunction "1_1") (pintype "passive"))
      (node (ref "U1") (pin "4") (pinfunction "COL_4") (pintype "passive"))
    )
    (net (code "80") (name "Net-(U3-VDD)") (class "Default")
      (node (ref "C4") (pin "1") (pinfunction "1_1") (pintype "passive"))
      (node (ref "R4") (pin "1") (pinfunction "1_1") (pintype "passive"))
      (node (ref "R6") (pin "2") (pinfunction "2_2") (pintype "passive"))
      (node (ref "U3") (pin "4") (pinfunction "VDD_4") (pintype "passive"))
    )
    (net (code "81") (name "Net-(U5-UCap)") (class "Default")
      (node (ref "C12") (pin "2") (pinfunction "2_2") (pintype "passive"))
      (node (ref "U5") (pin "13") (pinfunction "UCap_13") (pintype "passive"))
    )
    (net (code "82") (name "Net-(USB1-5)") (class "Default")
      (node (ref "D1") (pin "1") (pintype "passive"))
      (node (ref "USB1") (pin "4") (pinfunction "5_4") (pintype "passive"))
    )
    (net (code "83") (name "Net-(USB1-9)") (class "Default")
      (node (ref "B1") (pin "3") (pintype "passive"))
      (node (ref "C1") (pin "1") (pinfunction "1_1") (pintype "passive"))
      (node (ref "C3") (pin "1") (pintype "passive"))
      (node (ref "R2") (pin "1") (pinfunction "1_1") (pintype "passive"))
      (node (ref "R3") (pin "2") (pinfunction "2_2") (pintype "passive"))
      (node (ref "USB1") (pin "1") (pinfunction "9_1") (pintype "passive"))
    )
    (net (code "84") (name "Net-(USB1-10)") (class "Default")
      (node (ref "D2") (pin "1") (pintype "passive"))
      (node (ref "U3") (pin "5") (pinfunction "DRAIN_5") (pintype "passive"))
      (node (ref "U3") (pin "6") (pinfunction "DRAIN_6") (pintype "passive"))
      (node (ref "U3") (pin "7") (pinfunction "DRAIN_7") (pintype "passive"))
      (node (ref "U3") (pin "8") (pinfunction "DRAIN_8") (pintype "passive"))
      (node (ref "USB1") (pin "2") (pinfunction "8_2") (pintype "passive"))
      (node (ref "USB1") (pin "3") (pinfunction "10_3") (pintype "passive"))
    )
    (net (code "85") (name "unconnected-(K1-Pad1)") (class "Default")
      (node (ref "K1") (pin "1") (pinfunction "1_1") (pintype "passive"))
    )
    (net (code "86") (name "unconnected-(K1-Pad3)") (class "Default")
      (node (ref "K1") (pin "3") (pinfunction "3_3") (pintype "passive"))
    )
    (net (code "87") (name "unconnected-(K2-Pad1)") (class "Default")
      (node (ref "K2") (pin "1") (pinfunction "1_1") (pintype "passive"))
    )
    (net (code "88") (name "unconnected-(K2-Pad3)") (class "Default")
      (node (ref "K2") (pin "3") (pinfunction "3_3") (pintype "passive"))
    )
    (net (code "89") (name "unconnected-(K3-Pad1)") (class "Default")
      (node (ref "K3") (pin "1") (pinfunction "1_1") (pintype "passive"))
    )
    (net (code "90") (name "unconnected-(K3-Pad3)") (class "Default")
      (node (ref "K3") (pin "3") (pinfunction "3_3") (pintype "passive"))
    )
    (net (code "91") (name "unconnected-(K4-Pad1)") (class "Default")
      (node (ref "K4") (pin "1") (pinfunction "1_1") (pintype "passive"))
    )
    (net (code "92") (name "unconnected-(K4-Pad3)") (class "Default")
      (node (ref "K4") (pin "3") (pinfunction "3_3") (pintype "passive"))
    )
    (net (code "93") (name "unconnected-(U5-P4.0{slash}MOSI_3-Pad18)") (class "Default")
      (node (ref "U5") (pin "18") (pinfunction "P4.0/MOSI_3_18") (pintype "passive"))
    )
    (net (code "94") (name "unconnected-(U5-P5.1{slash}TxD3_2{slash}CMP+_3-Pad25)") (class "Default")
      (node (ref "U5") (pin "25") (pinfunction "P5.1/TxD3_2/CMP+_3_25") (pintype "passive+no_connect"))
    )
    (net (code "95") (name "unconnected-(U5-P5.4{slash}NRST{slash}MCLKO{slash}SS{slash}SS_3{slash}PWM2P{slash}PWM6_2{slash}ADC2{slash}T2-Pad14)") (class "Default")
      (node (ref "U5") (pin "14") (pinfunction "P5.4/NRST/MCLKO/SS/SS_3/PWM2P/PWM6_2/ADC2/T2_14") (pintype "passive+no_connect"))
    )
    (net (code "96") (name "unconnected-(U5-T3{slash}ADC12{slash}AD4{slash}P0.4-Pad47)") (class "Default")
      (node (ref "U5") (pin "47") (pinfunction "T3/ADC12/AD4/P0.4_47") (pintype "passive+no_connect"))
    )
    (net (code "97") (name "unconnected-(U5-T4CLKO_2{slash}PWM8_3{slash}TxD4{slash}ADC11{slash}AD3{slash}P0.3-Pad46)") (class "Default")
      (node (ref "U5") (pin "46") (pinfunction "T4CLKO_2/PWM8_3/TxD4/ADC11/AD3/P0.3_46") (pintype "passive+no_connect"))
    )
    (net (code "98") (name "unconnected-(U5-T4CLKO{slash}AD7{slash}P0.7-Pad4)") (class "Default")
      (node (ref "U5") (pin "4") (pinfunction "T4CLKO/AD7/P0.7_4") (pintype "passive+no_connect"))
    )
    (net (code "99") (name "unconnected-(U5-T4_2{slash}PWM7_3{slash}RxD4{slash}ADC10{slash}AD2{slash}P0.2-Pad45)") (class "Default")
      (node (ref "U5") (pin "45") (pinfunction "T4_2/PWM7_3/RxD4/ADC10/AD2/P0.2_45") (pintype "passive+no_connect"))
    )
    (net (code "100") (name "unconnected-(USB1-1-Pad7)") (class "Default")
      (node (ref "USB1") (pin "7") (pinfunction "1_7") (pintype "passive"))
    )
    (net (code "101") (name "unconnected-(USB1-4-Pad5)") (class "Default")
      (node (ref "USB1") (pin "5") (pinfunction "4_5") (pintype "passive"))
    )
  )
)
